# EKG_Modul_I.net
KiCad netlist of a schematic drawn in EAGLE
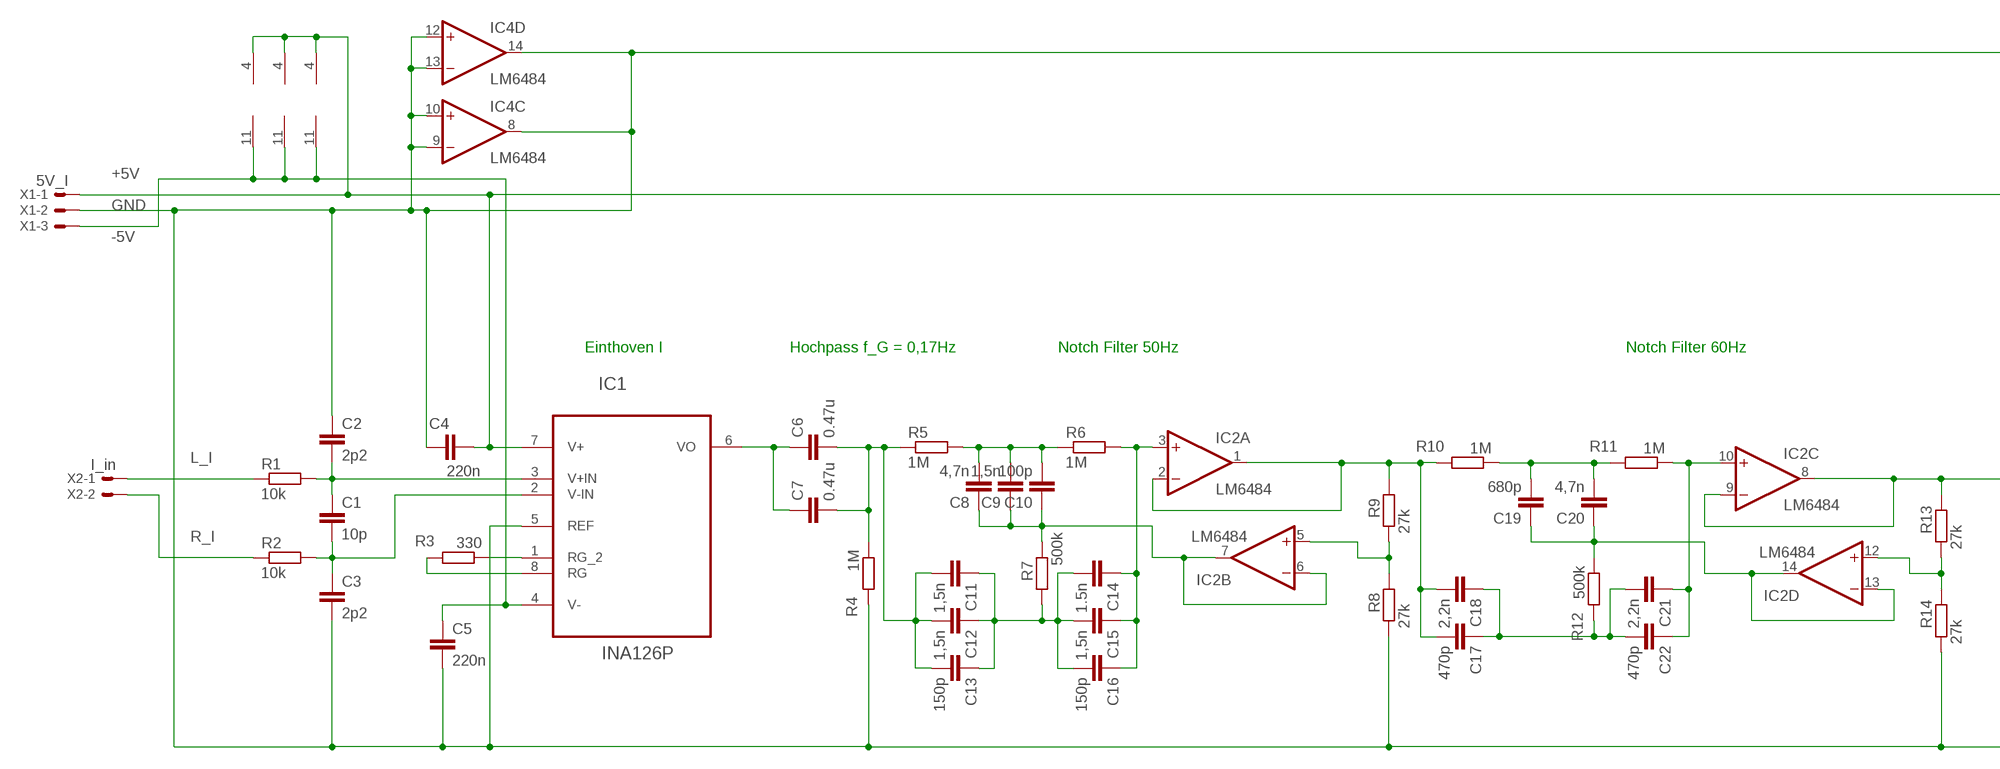
[diagram p0: schematic, sheet 1, part 1 of 2]
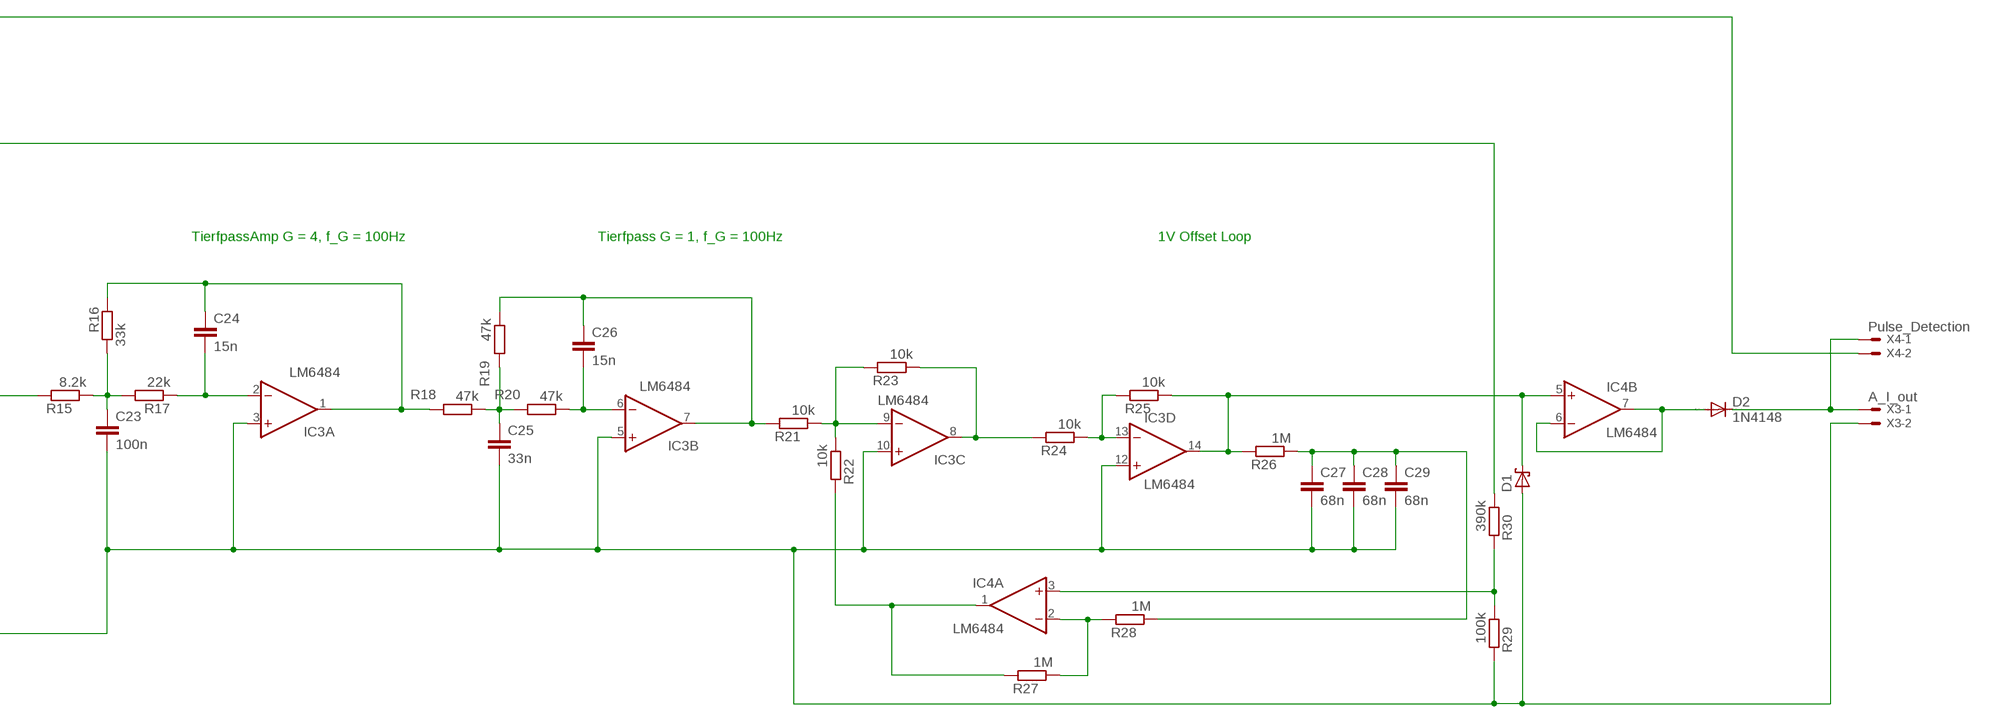
[diagram p1: schematic, sheet 1, part 2 of 2]

(export (version "E")
  (design (tool "Eeschema 10.0.6"))
  (components
    (comp (ref "C1")
      (value "10p")
      (footprint "eagle-import:C2.5-2")
      (libsource (lib "eagle-import") (part "C2.5/2"))
    )
    (comp (ref "C2")
      (value "2p2")
      (footprint "eagle-import:C2.5-2")
      (libsource (lib "eagle-import") (part "C2.5/2"))
    )
    (comp (ref "C3")
      (value "2p2")
      (footprint "eagle-import:C2.5-2")
      (libsource (lib "eagle-import") (part "C2.5/2"))
    )
    (comp (ref "C4")
      (value "220n")
      (footprint "eagle-import:C2.5-2")
      (libsource (lib "eagle-import") (part "C2.5/2"))
    )
    (comp (ref "C5")
      (value "220n")
      (footprint "eagle-import:C2.5-2")
      (libsource (lib "eagle-import") (part "C2.5/2"))
    )
    (comp (ref "C6")
      (value "0.47u")
      (footprint "eagle-import:C15B5")
      (libsource (lib "eagle-import") (part "C15/5"))
    )
    (comp (ref "C7")
      (value "0.47u")
      (footprint "eagle-import:C15B5")
      (libsource (lib "eagle-import") (part "C15/5"))
    )
    (comp (ref "C8")
      (value "4,7n")
      (footprint "eagle-import:C2.5-2")
      (libsource (lib "eagle-import") (part "C2.5/2"))
    )
    (comp (ref "C9")
      (value "1,5n")
      (footprint "eagle-import:C2.5-2")
      (libsource (lib "eagle-import") (part "C2.5/2"))
    )
    (comp (ref "C10")
      (value "100p")
      (footprint "eagle-import:C2.5-2")
      (libsource (lib "eagle-import") (part "C2.5/2"))
    )
    (comp (ref "C11")
      (value "1,5n")
      (footprint "eagle-import:C2.5-2")
      (libsource (lib "eagle-import") (part "C2.5/2"))
    )
    (comp (ref "C12")
      (value "1,5n")
      (footprint "eagle-import:C2.5-2")
      (libsource (lib "eagle-import") (part "C2.5/2"))
    )
    (comp (ref "C13")
      (value "150p")
      (footprint "eagle-import:C2.5-2")
      (libsource (lib "eagle-import") (part "C2.5/2"))
    )
    (comp (ref "C14")
      (value "1.5n")
      (footprint "eagle-import:C2.5-2")
      (libsource (lib "eagle-import") (part "C2.5/2"))
    )
    (comp (ref "C15")
      (value "1,5n")
      (footprint "eagle-import:C2.5-2")
      (libsource (lib "eagle-import") (part "C2.5/2"))
    )
    (comp (ref "C16")
      (value "150p")
      (footprint "eagle-import:C2.5-2")
      (libsource (lib "eagle-import") (part "C2.5/2"))
    )
    (comp (ref "C17")
      (value "470p")
      (footprint "eagle-import:C2.5-2")
      (libsource (lib "eagle-import") (part "C2.5/2"))
    )
    (comp (ref "C18")
      (value "2,2n")
      (footprint "eagle-import:C2.5-2")
      (libsource (lib "eagle-import") (part "C2.5/2"))
    )
    (comp (ref "C19")
      (value "680p")
      (footprint "eagle-import:C2.5-2")
      (libsource (lib "eagle-import") (part "C2.5/2"))
    )
    (comp (ref "C20")
      (value "4,7n")
      (footprint "eagle-import:C2.5-2")
      (libsource (lib "eagle-import") (part "C2.5/2"))
    )
    (comp (ref "C21")
      (value "2,2n")
      (footprint "eagle-import:C2.5-2")
      (libsource (lib "eagle-import") (part "C2.5/2"))
    )
    (comp (ref "C22")
      (value "470p")
      (footprint "eagle-import:C2.5-2")
      (libsource (lib "eagle-import") (part "C2.5/2"))
    )
    (comp (ref "C23")
      (value "100n")
      (footprint "eagle-import:C2.5-2")
      (libsource (lib "eagle-import") (part "C2.5/2"))
    )
    (comp (ref "C24")
      (value "15n")
      (footprint "eagle-import:C2.5-2")
      (libsource (lib "eagle-import") (part "C2.5/2"))
    )
    (comp (ref "C25")
      (value "33n")
      (footprint "eagle-import:C2.5-2")
      (libsource (lib "eagle-import") (part "C2.5/2"))
    )
    (comp (ref "C26")
      (value "15n")
      (footprint "eagle-import:C2.5-2")
      (libsource (lib "eagle-import") (part "C2.5/2"))
    )
    (comp (ref "C27")
      (value "68n")
      (footprint "eagle-import:C2.5-2")
      (libsource (lib "eagle-import") (part "C2.5/2"))
    )
    (comp (ref "C28")
      (value "68n")
      (footprint "eagle-import:C2.5-2")
      (libsource (lib "eagle-import") (part "C2.5/2"))
    )
    (comp (ref "C29")
      (value "68n")
      (footprint "eagle-import:C2.5-2")
      (libsource (lib "eagle-import") (part "C2.5/2"))
    )
    (comp (ref "D1")
      (value "SCHOTTKY-DIODEDO35-7")
      (footprint "eagle-import:DO35-7")
      (libsource (lib "eagle-import") (part "SCHOTTKY-DIODEDO35-7"))
    )
    (comp (ref "D2")
      (value "1N4148")
      (footprint "eagle-import:DO35-7")
      (libsource (lib "eagle-import") (part "1N4148DO35-7"))
    )
    (comp (ref "IC1")
      (value "INA126P")
      (footprint "eagle-import:DIP254P762X508-8")
      (fields (field (name "MF") "Texas Instruments"))
      (libsource (lib "eagle-import") (part "INA126P"))
    )
    (comp (ref "IC2")
      (value "LM6484")
      (footprint "eagle-import:DIL14")
      (libsource (lib "eagle-import") (part "QUAD_OPAMPP"))
    )
    (comp (ref "IC3")
      (value "LM6484")
      (footprint "eagle-import:DIL14")
      (libsource (lib "eagle-import") (part "QUAD_OPAMPP"))
    )
    (comp (ref "IC4")
      (value "LM6484")
      (footprint "eagle-import:DIL14")
      (libsource (lib "eagle-import") (part "QUAD_OPAMPP"))
    )
    (comp (ref "R1")
      (value "10k")
      (footprint "eagle-import:0207_7")
      (libsource (lib "eagle-import") (part "R-EU_0207/7"))
    )
    (comp (ref "R2")
      (value "10k")
      (footprint "eagle-import:0207_7")
      (libsource (lib "eagle-import") (part "R-EU_0207/7"))
    )
    (comp (ref "R3")
      (value "330")
      (footprint "eagle-import:0207_7")
      (libsource (lib "eagle-import") (part "R-EU_0207/7"))
    )
    (comp (ref "R4")
      (value "1M")
      (footprint "eagle-import:0207_7")
      (libsource (lib "eagle-import") (part "R-EU_0207/7"))
    )
    (comp (ref "R5")
      (value "1M")
      (footprint "eagle-import:0207_7")
      (libsource (lib "eagle-import") (part "R-EU_0207/7"))
    )
    (comp (ref "R6")
      (value "1M")
      (footprint "eagle-import:0207_7")
      (libsource (lib "eagle-import") (part "R-EU_0207/7"))
    )
    (comp (ref "R7")
      (value "500k")
      (footprint "eagle-import:0207_7")
      (libsource (lib "eagle-import") (part "R-EU_0207/7"))
    )
    (comp (ref "R8")
      (value "27k")
      (footprint "eagle-import:0207_7")
      (libsource (lib "eagle-import") (part "R-EU_0207/7"))
    )
    (comp (ref "R9")
      (value "27k")
      (footprint "eagle-import:0207_7")
      (libsource (lib "eagle-import") (part "R-EU_0207/7"))
    )
    (comp (ref "R10")
      (value "1M")
      (footprint "eagle-import:0207_7")
      (libsource (lib "eagle-import") (part "R-EU_0207/7"))
    )
    (comp (ref "R11")
      (value "1M")
      (footprint "eagle-import:0207_7")
      (libsource (lib "eagle-import") (part "R-EU_0207/7"))
    )
    (comp (ref "R12")
      (value "500k")
      (footprint "eagle-import:0207_7")
      (libsource (lib "eagle-import") (part "R-EU_0207/7"))
    )
    (comp (ref "R13")
      (value "27k")
      (footprint "eagle-import:0207_7")
      (libsource (lib "eagle-import") (part "R-EU_0207/7"))
    )
    (comp (ref "R14")
      (value "27k")
      (footprint "eagle-import:0207_7")
      (libsource (lib "eagle-import") (part "R-EU_0207/7"))
    )
    (comp (ref "R15")
      (value "8.2k")
      (footprint "eagle-import:0207_7")
      (libsource (lib "eagle-import") (part "R-EU_0207/7"))
    )
    (comp (ref "R16")
      (value "33k")
      (footprint "eagle-import:0207_7")
      (libsource (lib "eagle-import") (part "R-EU_0207/7"))
    )
    (comp (ref "R17")
      (value "22k")
      (footprint "eagle-import:0207_7")
      (libsource (lib "eagle-import") (part "R-EU_0207/7"))
    )
    (comp (ref "R18")
      (value "47k")
      (footprint "eagle-import:0207_7")
      (libsource (lib "eagle-import") (part "R-EU_0207/7"))
    )
    (comp (ref "R19")
      (value "47k")
      (footprint "eagle-import:0207_7")
      (libsource (lib "eagle-import") (part "R-EU_0207/7"))
    )
    (comp (ref "R20")
      (value "47k")
      (footprint "eagle-import:0207_7")
      (libsource (lib "eagle-import") (part "R-EU_0207/7"))
    )
    (comp (ref "R21")
      (value "10k")
      (footprint "eagle-import:0207_7")
      (libsource (lib "eagle-import") (part "R-EU_0207/7"))
    )
    (comp (ref "R22")
      (value "10k")
      (footprint "eagle-import:0207_7")
      (libsource (lib "eagle-import") (part "R-EU_0207/7"))
    )
    (comp (ref "R23")
      (value "10k")
      (footprint "eagle-import:0207_7")
      (libsource (lib "eagle-import") (part "R-EU_0207/7"))
    )
    (comp (ref "R24")
      (value "10k")
      (footprint "eagle-import:0207_7")
      (libsource (lib "eagle-import") (part "R-EU_0207/7"))
    )
    (comp (ref "R25")
      (value "10k")
      (footprint "eagle-import:0207_7")
      (libsource (lib "eagle-import") (part "R-EU_0207/7"))
    )
    (comp (ref "R26")
      (value "1M")
      (footprint "eagle-import:0207_7")
      (libsource (lib "eagle-import") (part "R-EU_0207/7"))
    )
    (comp (ref "R27")
      (value "1M")
      (footprint "eagle-import:0207_7")
      (libsource (lib "eagle-import") (part "R-EU_0207/7"))
    )
    (comp (ref "R28")
      (value "1M")
      (footprint "eagle-import:0207_7")
      (libsource (lib "eagle-import") (part "R-EU_0207/7"))
    )
    (comp (ref "R29")
      (value "100k")
      (footprint "eagle-import:0207_7")
      (libsource (lib "eagle-import") (part "R-EU_0207/7"))
    )
    (comp (ref "R30")
      (value "390k")
      (footprint "eagle-import:0207_7")
      (libsource (lib "eagle-import") (part "R-EU_0207/7"))
    )
    (comp (ref "X1")
      (value "5V_I")
      (footprint "eagle-import:JST-XH-03-PACKAGE-LONG-PAD")
      (libsource (lib "eagle-import") (part "JST-XH-03-PIN-LONG-PAD"))
    )
    (comp (ref "X2")
      (value "I_in")
      (footprint "eagle-import:JST-XH-02-PACKAGE-LONG-PAD")
      (libsource (lib "eagle-import") (part "JST-XH-02-PIN-LONG-PAD"))
    )
    (comp (ref "X3")
      (value "A_I_out")
      (footprint "eagle-import:JST-XH-02-PACKAGE-LONG-PAD")
      (libsource (lib "eagle-import") (part "JST-XH-02-PIN-LONG-PAD"))
    )
    (comp (ref "X4")
      (value "Pulse_Detection")
      (footprint "eagle-import:JST-XH-02-PACKAGE-LONG-PAD")
      (libsource (lib "eagle-import") (part "JST-XH-02-PIN-LONG-PAD"))
    )
  )
  (nets
    (net (code "1") (name "/+5V") (class "Default")
      (node (ref "C4") (pin "2") (pinfunction "2_2") (pintype "passive"))
      (node (ref "IC1") (pin "7") (pinfunction "V+_7") (pintype "power_in"))
      (node (ref "IC2") (pin "4") (pinfunction "V+_4") (pintype "power_in"))
      (node (ref "IC3") (pin "4") (pinfunction "V+_4") (pintype "power_in"))
      (node (ref "IC4") (pin "4") (pinfunction "V+_4") (pintype "power_in"))
      (node (ref "R30") (pin "1") (pinfunction "1_1") (pintype "passive"))
      (node (ref "X1") (pin "1") (pinfunction "S_1") (pintype "passive"))
    )
    (net (code "2") (name "/-5V") (class "Default")
      (node (ref "C5") (pin "1") (pinfunction "1_1") (pintype "passive"))
      (node (ref "IC1") (pin "4") (pinfunction "V-_4") (pintype "power_in"))
      (node (ref "IC2") (pin "11") (pinfunction "V-_11") (pintype "power_in"))
      (node (ref "IC3") (pin "11") (pinfunction "V-_11") (pintype "power_in"))
      (node (ref "IC4") (pin "11") (pinfunction "V-_11") (pintype "power_in"))
      (node (ref "X1") (pin "3") (pinfunction "S_3") (pintype "passive"))
    )
    (net (code "3") (name "/GND") (class "Default")
      (node (ref "C2") (pin "1") (pinfunction "1_1") (pintype "passive"))
      (node (ref "C23") (pin "2") (pinfunction "2_2") (pintype "passive"))
      (node (ref "C25") (pin "2") (pinfunction "2_2") (pintype "passive"))
      (node (ref "C27") (pin "2") (pinfunction "2_2") (pintype "passive"))
      (node (ref "C28") (pin "2") (pinfunction "2_2") (pintype "passive"))
      (node (ref "C29") (pin "2") (pinfunction "2_2") (pintype "passive"))
      (node (ref "C3") (pin "2") (pinfunction "2_2") (pintype "passive"))
      (node (ref "C4") (pin "1") (pinfunction "1_1") (pintype "passive"))
      (node (ref "C5") (pin "2") (pinfunction "2_2") (pintype "passive"))
      (node (ref "D1") (pin "A") (pinfunction "A_A") (pintype "passive"))
      (node (ref "IC1") (pin "5") (pinfunction "REF_5") (pintype "passive"))
      (node (ref "IC3") (pin "10") (pinfunction "+IN_10") (pintype "input"))
      (node (ref "IC3") (pin "12") (pinfunction "+IN_12") (pintype "input"))
      (node (ref "IC3") (pin "3") (pinfunction "+IN_3") (pintype "input"))
      (node (ref "IC3") (pin "5") (pinfunction "+IN_5") (pintype "input"))
      (node (ref "IC4") (pin "10") (pinfunction "+IN_10") (pintype "input"))
      (node (ref "IC4") (pin "12") (pinfunction "+IN_12") (pintype "input"))
      (node (ref "IC4") (pin "13") (pinfunction "-IN_13") (pintype "input"))
      (node (ref "IC4") (pin "14") (pinfunction "OUT_14") (pintype "output"))
      (node (ref "IC4") (pin "8") (pinfunction "OUT_8") (pintype "output"))
      (node (ref "IC4") (pin "9") (pinfunction "-IN_9") (pintype "input"))
      (node (ref "R14") (pin "1") (pinfunction "1_1") (pintype "passive"))
      (node (ref "R29") (pin "2") (pinfunction "2_2") (pintype "passive"))
      (node (ref "R4") (pin "2") (pinfunction "2_2") (pintype "passive"))
      (node (ref "R8") (pin "1") (pinfunction "1_1") (pintype "passive"))
      (node (ref "X1") (pin "2") (pinfunction "S_2") (pintype "passive"))
      (node (ref "X3") (pin "2") (pinfunction "S_2") (pintype "passive"))
      (node (ref "X4") (pin "2") (pinfunction "S_2") (pintype "passive"))
    )
    (net (code "4") (name "/L_I") (class "Default")
      (node (ref "R1") (pin "1") (pinfunction "1_1") (pintype "passive"))
      (node (ref "X2") (pin "1") (pinfunction "S_1") (pintype "passive"))
    )
    (net (code "5") (name "/R_I") (class "Default")
      (node (ref "R2") (pin "1") (pinfunction "1_1") (pintype "passive"))
      (node (ref "X2") (pin "2") (pinfunction "S_2") (pintype "passive"))
    )
    (net (code "6") (name "Net-(C10-Pad2)") (class "Default")
      (node (ref "C10") (pin "2") (pinfunction "2_2") (pintype "passive"))
      (node (ref "C8") (pin "2") (pinfunction "2_2") (pintype "passive"))
      (node (ref "C9") (pin "2") (pinfunction "2_2") (pintype "passive"))
      (node (ref "R5") (pin "2") (pinfunction "2_2") (pintype "passive"))
      (node (ref "R6") (pin "1") (pinfunction "1_1") (pintype "passive"))
    )
    (net (code "7") (name "Net-(C11-Pad1)") (class "Default")
      (node (ref "C11") (pin "1") (pinfunction "1_1") (pintype "passive"))
      (node (ref "C12") (pin "1") (pinfunction "1_1") (pintype "passive"))
      (node (ref "C13") (pin "1") (pinfunction "1_1") (pintype "passive"))
      (node (ref "C14") (pin "2") (pinfunction "2_2") (pintype "passive"))
      (node (ref "C15") (pin "2") (pinfunction "2_2") (pintype "passive"))
      (node (ref "C16") (pin "2") (pinfunction "2_2") (pintype "passive"))
      (node (ref "R7") (pin "1") (pinfunction "1_1") (pintype "passive"))
    )
    (net (code "8") (name "Net-(C11-Pad2)") (class "Default")
      (node (ref "C11") (pin "2") (pinfunction "2_2") (pintype "passive"))
      (node (ref "C12") (pin "2") (pinfunction "2_2") (pintype "passive"))
      (node (ref "C13") (pin "2") (pinfunction "2_2") (pintype "passive"))
      (node (ref "C6") (pin "2") (pinfunction "2_2") (pintype "passive"))
      (node (ref "C7") (pin "2") (pinfunction "2_2") (pintype "passive"))
      (node (ref "R4") (pin "1") (pinfunction "1_1") (pintype "passive"))
      (node (ref "R5") (pin "1") (pinfunction "1_1") (pintype "passive"))
    )
    (net (code "9") (name "Net-(C17-Pad1)") (class "Default")
      (node (ref "C17") (pin "1") (pinfunction "1_1") (pintype "passive"))
      (node (ref "C18") (pin "1") (pinfunction "1_1") (pintype "passive"))
      (node (ref "C21") (pin "2") (pinfunction "2_2") (pintype "passive"))
      (node (ref "C22") (pin "2") (pinfunction "2_2") (pintype "passive"))
      (node (ref "R12") (pin "2") (pinfunction "2_2") (pintype "passive"))
    )
    (net (code "10") (name "Net-(C19-Pad2)") (class "Default")
      (node (ref "C19") (pin "2") (pinfunction "2_2") (pintype "passive"))
      (node (ref "C20") (pin "2") (pinfunction "2_2") (pintype "passive"))
      (node (ref "R10") (pin "1") (pinfunction "1_1") (pintype "passive"))
      (node (ref "R11") (pin "2") (pinfunction "2_2") (pintype "passive"))
    )
    (net (code "11") (name "Net-(C23-Pad1)") (class "Default")
      (node (ref "C23") (pin "1") (pinfunction "1_1") (pintype "passive"))
      (node (ref "R15") (pin "1") (pinfunction "1_1") (pintype "passive"))
      (node (ref "R16") (pin "1") (pinfunction "1_1") (pintype "passive"))
      (node (ref "R17") (pin "2") (pinfunction "2_2") (pintype "passive"))
    )
    (net (code "12") (name "Net-(C25-Pad1)") (class "Default")
      (node (ref "C25") (pin "1") (pinfunction "1_1") (pintype "passive"))
      (node (ref "R18") (pin "1") (pinfunction "1_1") (pintype "passive"))
      (node (ref "R19") (pin "2") (pinfunction "2_2") (pintype "passive"))
      (node (ref "R20") (pin "2") (pinfunction "2_2") (pintype "passive"))
    )
    (net (code "13") (name "Net-(C27-Pad1)") (class "Default")
      (node (ref "C27") (pin "1") (pinfunction "1_1") (pintype "passive"))
      (node (ref "C28") (pin "1") (pinfunction "1_1") (pintype "passive"))
      (node (ref "C29") (pin "1") (pinfunction "1_1") (pintype "passive"))
      (node (ref "R26") (pin "1") (pinfunction "1_1") (pintype "passive"))
      (node (ref "R28") (pin "1") (pinfunction "1_1") (pintype "passive"))
    )
    (net (code "14") (name "Net-(IC1-RG)") (class "Default")
      (node (ref "IC1") (pin "8") (pinfunction "RG_8") (pintype "passive"))
      (node (ref "R3") (pin "2") (pinfunction "2_2") (pintype "passive"))
    )
    (net (code "15") (name "Net-(IC1-RG_2)") (class "Default")
      (node (ref "IC1") (pin "1") (pinfunction "RG_2_1") (pintype "passive"))
      (node (ref "R3") (pin "1") (pinfunction "1_1") (pintype "passive"))
    )
    (net (code "16") (name "Net-(IC1-V+IN)") (class "Default")
      (node (ref "C1") (pin "1") (pinfunction "1_1") (pintype "passive"))
      (node (ref "C2") (pin "2") (pinfunction "2_2") (pintype "passive"))
      (node (ref "IC1") (pin "3") (pinfunction "V+IN_3") (pintype "input"))
      (node (ref "R1") (pin "2") (pinfunction "2_2") (pintype "passive"))
    )
    (net (code "17") (name "Net-(IC1-V-IN)") (class "Default")
      (node (ref "C1") (pin "2") (pinfunction "2_2") (pintype "passive"))
      (node (ref "C3") (pin "1") (pinfunction "1_1") (pintype "passive"))
      (node (ref "IC1") (pin "2") (pinfunction "V-IN_2") (pintype "input"))
      (node (ref "R2") (pin "2") (pinfunction "2_2") (pintype "passive"))
    )
    (net (code "18") (name "Net-(IC1-VO)") (class "Default")
      (node (ref "C6") (pin "1") (pinfunction "1_1") (pintype "passive"))
      (node (ref "C7") (pin "1") (pinfunction "1_1") (pintype "passive"))
      (node (ref "IC1") (pin "6") (pinfunction "VO_6") (pintype "output"))
    )
    (net (code "19") (name "Net-(IC2A-+IN)") (class "Default")
      (node (ref "C14") (pin "1") (pinfunction "1_1") (pintype "passive"))
      (node (ref "C15") (pin "1") (pinfunction "1_1") (pintype "passive"))
      (node (ref "C16") (pin "1") (pinfunction "1_1") (pintype "passive"))
      (node (ref "IC2") (pin "3") (pinfunction "+IN_3") (pintype "input"))
      (node (ref "R6") (pin "2") (pinfunction "2_2") (pintype "passive"))
    )
    (net (code "20") (name "Net-(IC2A--IN)") (class "Default")
      (node (ref "C17") (pin "2") (pinfunction "2_2") (pintype "passive"))
      (node (ref "C18") (pin "2") (pinfunction "2_2") (pintype "passive"))
      (node (ref "IC2") (pin "1") (pinfunction "OUT_1") (pintype "output"))
      (node (ref "IC2") (pin "2") (pinfunction "-IN_2") (pintype "input"))
      (node (ref "R10") (pin "2") (pinfunction "2_2") (pintype "passive"))
      (node (ref "R9") (pin "2") (pinfunction "2_2") (pintype "passive"))
    )
    (net (code "21") (name "Net-(IC2B-+IN)") (class "Default")
      (node (ref "IC2") (pin "5") (pinfunction "+IN_5") (pintype "input"))
      (node (ref "R8") (pin "2") (pinfunction "2_2") (pintype "passive"))
      (node (ref "R9") (pin "1") (pinfunction "1_1") (pintype "passive"))
    )
    (net (code "22") (name "Net-(IC2B--IN)") (class "Default")
      (node (ref "C10") (pin "1") (pinfunction "1_1") (pintype "passive"))
      (node (ref "C8") (pin "1") (pinfunction "1_1") (pintype "passive"))
      (node (ref "C9") (pin "1") (pinfunction "1_1") (pintype "passive"))
      (node (ref "IC2") (pin "6") (pinfunction "-IN_6") (pintype "input"))
      (node (ref "IC2") (pin "7") (pinfunction "OUT_7") (pintype "output"))
      (node (ref "R7") (pin "2") (pinfunction "2_2") (pintype "passive"))
    )
    (net (code "23") (name "Net-(IC2C-+IN)") (class "Default")
      (node (ref "C21") (pin "1") (pinfunction "1_1") (pintype "passive"))
      (node (ref "C22") (pin "1") (pinfunction "1_1") (pintype "passive"))
      (node (ref "IC2") (pin "10") (pinfunction "+IN_10") (pintype "input"))
      (node (ref "R11") (pin "1") (pinfunction "1_1") (pintype "passive"))
    )
    (net (code "24") (name "Net-(IC2C--IN)") (class "Default")
      (node (ref "IC2") (pin "8") (pinfunction "OUT_8") (pintype "output"))
      (node (ref "IC2") (pin "9") (pinfunction "-IN_9") (pintype "input"))
      (node (ref "R13") (pin "2") (pinfunction "2_2") (pintype "passive"))
      (node (ref "R15") (pin "2") (pinfunction "2_2") (pintype "passive"))
    )
    (net (code "25") (name "Net-(IC2D-+IN)") (class "Default")
      (node (ref "IC2") (pin "12") (pinfunction "+IN_12") (pintype "input"))
      (node (ref "R13") (pin "1") (pinfunction "1_1") (pintype "passive"))
      (node (ref "R14") (pin "2") (pinfunction "2_2") (pintype "passive"))
    )
    (net (code "26") (name "Net-(IC2D--IN)") (class "Default")
      (node (ref "C19") (pin "1") (pinfunction "1_1") (pintype "passive"))
      (node (ref "C20") (pin "1") (pinfunction "1_1") (pintype "passive"))
      (node (ref "IC2") (pin "13") (pinfunction "-IN_13") (pintype "input"))
      (node (ref "IC2") (pin "14") (pinfunction "OUT_14") (pintype "output"))
      (node (ref "R12") (pin "1") (pinfunction "1_1") (pintype "passive"))
    )
    (net (code "27") (name "Net-(IC3A--IN)") (class "Default")
      (node (ref "C24") (pin "2") (pinfunction "2_2") (pintype "passive"))
      (node (ref "IC3") (pin "2") (pinfunction "-IN_2") (pintype "input"))
      (node (ref "R17") (pin "1") (pinfunction "1_1") (pintype "passive"))
    )
    (net (code "28") (name "Net-(IC3A-OUT)") (class "Default")
      (node (ref "C24") (pin "1") (pinfunction "1_1") (pintype "passive"))
      (node (ref "IC3") (pin "1") (pinfunction "OUT_1") (pintype "output"))
      (node (ref "R16") (pin "2") (pinfunction "2_2") (pintype "passive"))
      (node (ref "R18") (pin "2") (pinfunction "2_2") (pintype "passive"))
    )
    (net (code "29") (name "Net-(IC3B--IN)") (class "Default")
      (node (ref "C26") (pin "2") (pinfunction "2_2") (pintype "passive"))
      (node (ref "IC3") (pin "6") (pinfunction "-IN_6") (pintype "input"))
      (node (ref "R20") (pin "1") (pinfunction "1_1") (pintype "passive"))
    )
    (net (code "30") (name "Net-(IC3B-OUT)") (class "Default")
      (node (ref "C26") (pin "1") (pinfunction "1_1") (pintype "passive"))
      (node (ref "IC3") (pin "7") (pinfunction "OUT_7") (pintype "output"))
      (node (ref "R19") (pin "1") (pinfunction "1_1") (pintype "passive"))
      (node (ref "R21") (pin "2") (pinfunction "2_2") (pintype "passive"))
    )
    (net (code "31") (name "Net-(IC3C--IN)") (class "Default")
      (node (ref "IC3") (pin "9") (pinfunction "-IN_9") (pintype "input"))
      (node (ref "R21") (pin "1") (pinfunction "1_1") (pintype "passive"))
      (node (ref "R22") (pin "1") (pinfunction "1_1") (pintype "passive"))
      (node (ref "R23") (pin "2") (pinfunction "2_2") (pintype "passive"))
    )
    (net (code "32") (name "Net-(IC3C-OUT)") (class "Default")
      (node (ref "IC3") (pin "8") (pinfunction "OUT_8") (pintype "output"))
      (node (ref "R23") (pin "1") (pinfunction "1_1") (pintype "passive"))
      (node (ref "R24") (pin "2") (pinfunction "2_2") (pintype "passive"))
    )
    (net (code "33") (name "Net-(IC3D--IN)") (class "Default")
      (node (ref "IC3") (pin "13") (pinfunction "-IN_13") (pintype "input"))
      (node (ref "R24") (pin "1") (pinfunction "1_1") (pintype "passive"))
      (node (ref "R25") (pin "2") (pinfunction "2_2") (pintype "passive"))
    )
    (net (code "34") (name "Net-(IC3D-OUT)") (class "Default")
      (node (ref "D1") (pin "C") (pinfunction "C_C") (pintype "passive"))
      (node (ref "IC3") (pin "14") (pinfunction "OUT_14") (pintype "output"))
      (node (ref "IC4") (pin "5") (pinfunction "+IN_5") (pintype "input"))
      (node (ref "R25") (pin "1") (pinfunction "1_1") (pintype "passive"))
      (node (ref "R26") (pin "2") (pinfunction "2_2") (pintype "passive"))
    )
    (net (code "35") (name "Net-(IC4A-+IN)") (class "Default")
      (node (ref "IC4") (pin "3") (pinfunction "+IN_3") (pintype "input"))
      (node (ref "R29") (pin "1") (pinfunction "1_1") (pintype "passive"))
      (node (ref "R30") (pin "2") (pinfunction "2_2") (pintype "passive"))
    )
    (net (code "36") (name "Net-(IC4A--IN)") (class "Default")
      (node (ref "IC4") (pin "2") (pinfunction "-IN_2") (pintype "input"))
      (node (ref "R27") (pin "1") (pinfunction "1_1") (pintype "passive"))
      (node (ref "R28") (pin "2") (pinfunction "2_2") (pintype "passive"))
    )
    (net (code "37") (name "Net-(IC4A-OUT)") (class "Default")
      (node (ref "IC4") (pin "1") (pinfunction "OUT_1") (pintype "output"))
      (node (ref "R22") (pin "2") (pinfunction "2_2") (pintype "passive"))
      (node (ref "R27") (pin "2") (pinfunction "2_2") (pintype "passive"))
    )
    (net (code "38") (name "Net-(IC4B--IN)") (class "Default")
      (node (ref "D2") (pin "A") (pinfunction "A_A") (pintype "passive"))
      (node (ref "IC4") (pin "6") (pinfunction "-IN_6") (pintype "input"))
      (node (ref "IC4") (pin "7") (pinfunction "OUT_7") (pintype "output"))
    )
    (net (code "39") (name "Net-(X3A-S)") (class "Default")
      (node (ref "D2") (pin "C") (pinfunction "C_C") (pintype "passive"))
      (node (ref "X3") (pin "1") (pinfunction "S_1") (pintype "passive"))
      (node (ref "X4") (pin "1") (pinfunction "S_1") (pintype "passive"))
    )
  )
)
